# Sensado.net
KiCad netlist of a schematic drawn in Altium Designer
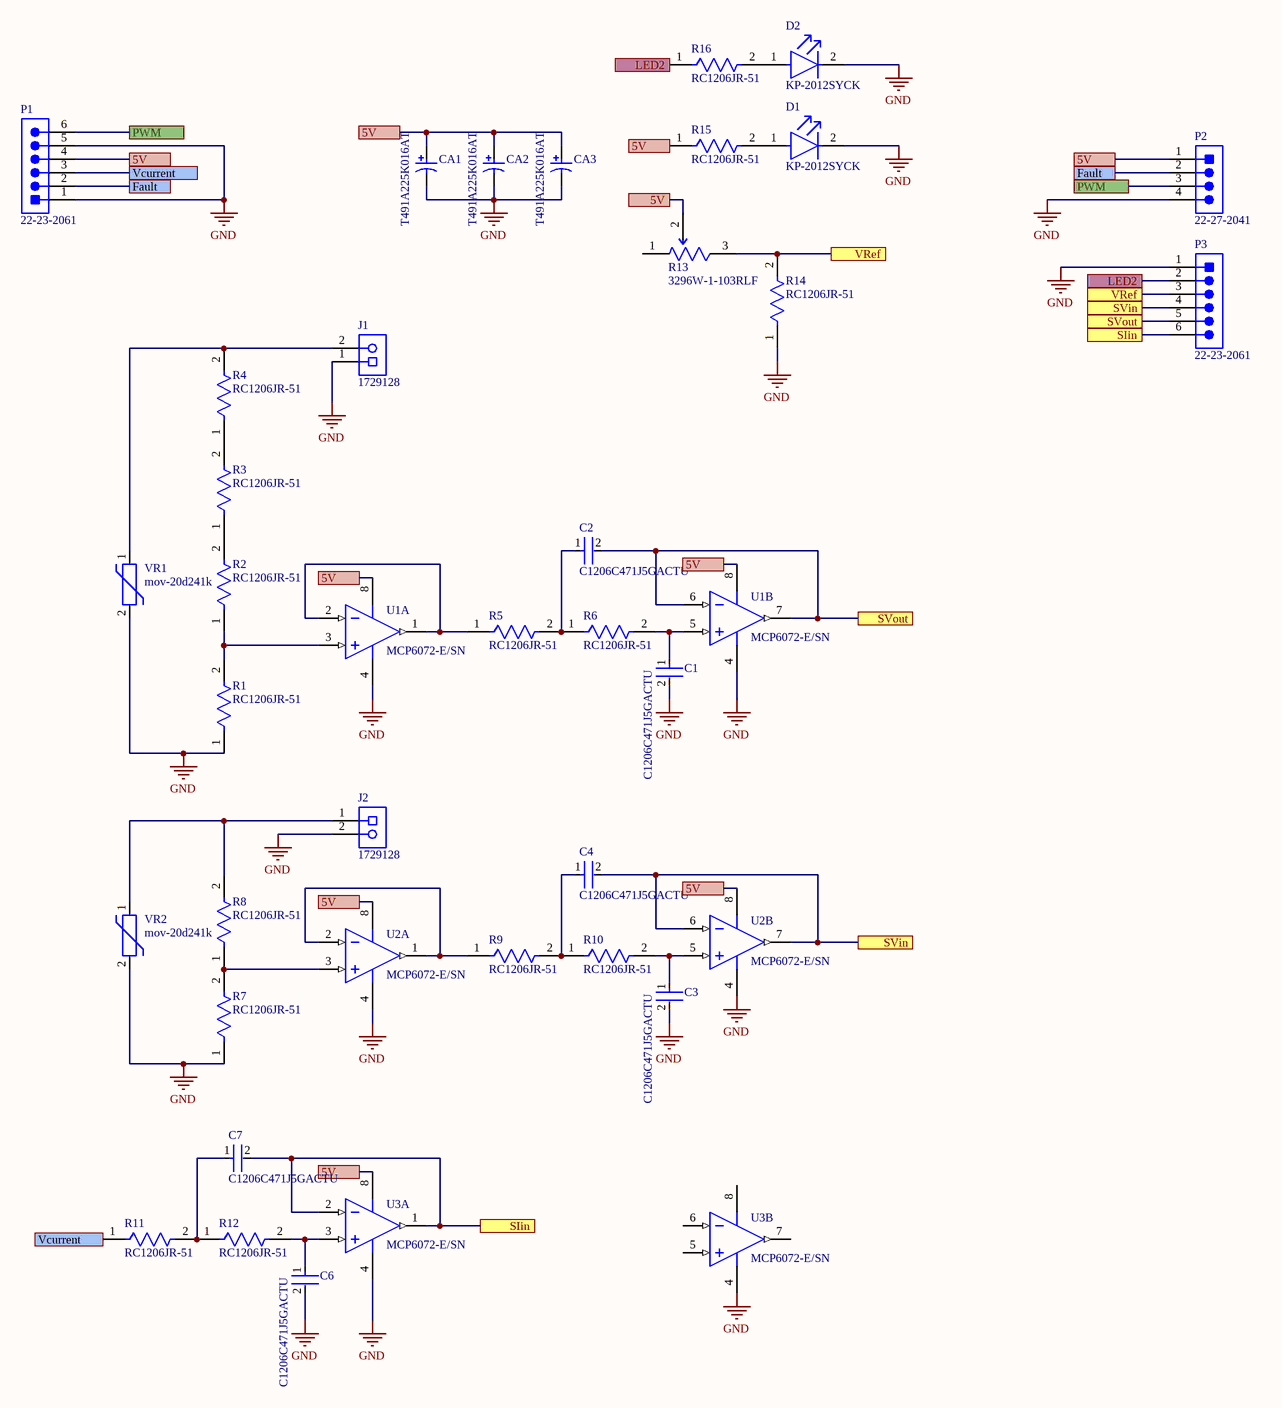
[diagram p0: Sensado.SchDoc]

(export (version "E")
  (design (tool "Eeschema 10.0.6"))
  (components
    (comp (ref "C1")
      (value "C1206C471J5GACTU")
      (footprint "FP-C1206C-EB-IPC_B")
      (description "1206 C 470pF Ceramic Multilayer Capacitor; 50 V; +125degC; C0G Dielectric; +/-5%")
      (fields
        (field (name "TOLERANCE") "0.05")
        (field (name "OCTOPART") "https://octopart.com/c1206c471j5gactu-kemet-123947")
      )
      (libsource (lib "Altium Content Vault") (part "b4654b650e69147ec39a6b967a45e02"))
    )
    (comp (ref "C2")
      (value "C1206C471J5GACTU")
      (footprint "FP-C1206C-EB-IPC_B")
      (description "1206 C 470pF Ceramic Multilayer Capacitor; 50 V; +125degC; C0G Dielectric; +/-5%")
      (fields
        (field (name "TOLERANCE") "0.05")
        (field (name "OCTOPART") "https://octopart.com/c1206c471j5gactu-kemet-123947")
      )
      (libsource (lib "Altium Content Vault") (part "b4654b650e69147ec39a6b967a45e02"))
    )
    (comp (ref "C3")
      (value "C1206C471J5GACTU")
      (footprint "FP-C1206C-EB-IPC_B")
      (description "1206 C 470pF Ceramic Multilayer Capacitor; 50 V; +125degC; C0G Dielectric; +/-5%")
      (fields
        (field (name "TOLERANCE") "0.05")
        (field (name "OCTOPART") "https://octopart.com/c1206c471j5gactu-kemet-123947")
      )
      (libsource (lib "Altium Content Vault") (part "b4654b650e69147ec39a6b967a45e02"))
    )
    (comp (ref "C4")
      (value "C1206C471J5GACTU")
      (footprint "FP-C1206C-EB-IPC_B")
      (description "1206 C 470pF Ceramic Multilayer Capacitor; 50 V; +125degC; C0G Dielectric; +/-5%")
      (fields
        (field (name "TOLERANCE") "0.05")
        (field (name "OCTOPART") "https://octopart.com/c1206c471j5gactu-kemet-123947")
      )
      (libsource (lib "Altium Content Vault") (part "b4654b650e69147ec39a6b967a45e02"))
    )
    (comp (ref "C6")
      (value "C1206C471J5GACTU")
      (footprint "FP-C1206C-EB-IPC_B")
      (description "1206 C 470pF Ceramic Multilayer Capacitor; 50 V; +125degC; C0G Dielectric; +/-5%")
      (fields
        (field (name "TOLERANCE") "0.05")
        (field (name "OCTOPART") "https://octopart.com/c1206c471j5gactu-kemet-123947")
      )
      (libsource (lib "Altium Content Vault") (part "b4654b650e69147ec39a6b967a45e02"))
    )
    (comp (ref "C7")
      (value "C1206C471J5GACTU")
      (footprint "FP-C1206C-EB-IPC_B")
      (description "1206 C 470pF Ceramic Multilayer Capacitor; 50 V; +125degC; C0G Dielectric; +/-5%")
      (fields
        (field (name "TOLERANCE") "0.05")
        (field (name "OCTOPART") "https://octopart.com/c1206c471j5gactu-kemet-123947")
      )
      (libsource (lib "Altium Content Vault") (part "b4654b650e69147ec39a6b967a45e02"))
    )
    (comp (ref "CA1")
      (value "T491A225K016AT")
      (footprint "KEMT-T491-A_N")
      (description "Tantalum Capacitor, 2.2 uF, +/- 10%, 16 V, -55 to 125 degC, 2-Pin SMD, RoHS, Tape and Reel")
      (fields (field (name "VOLTAGE") "16VDC") (field (name "MANUFACTURER") "Kemet"))
      (libsource (lib "Altium Content Vault") (part "CAP-P-2"))
    )
    (comp (ref "CA2")
      (value "T491A225K016AT")
      (footprint "KEMT-T491-A_N")
      (description "Tantalum Capacitor, 2.2 uF, +/- 10%, 16 V, -55 to 125 degC, 2-Pin SMD, RoHS, Tape and Reel")
      (fields (field (name "VOLTAGE") "16VDC") (field (name "MANUFACTURER") "Kemet"))
      (libsource (lib "Altium Content Vault") (part "CAP-P-2"))
    )
    (comp (ref "CA3")
      (value "T491A225K016AT")
      (footprint "KEMT-T491-A_N")
      (description "Tantalum Capacitor, 2.2 uF, +/- 10%, 16 V, -55 to 125 degC, 2-Pin SMD, RoHS, Tape and Reel")
      (fields (field (name "VOLTAGE") "16VDC") (field (name "MANUFACTURER") "Kemet"))
      (libsource (lib "Altium Content Vault") (part "CAP-P-2"))
    )
    (comp (ref "D1")
      (value "KP-2012SYCK")
      (footprint "FP-KP-2012SYCK-MFG")
      (description "2.0x1.25mm SMD CHIP LED LAMP")
      (fields
        (field (name "OCTOPART") "https://octopart.com/kp-2012syck-kingbright-5387420")
        (field (name "MANUFACTURER") "KINGBRIGHT")
      )
      (libsource (lib "Altium Content Vault") (part "ab1c01a81903e929fc6c44469aada92"))
    )
    (comp (ref "D2")
      (value "KP-2012SYCK")
      (footprint "FP-KP-2012SYCK-MFG")
      (description "2.0x1.25mm SMD CHIP LED LAMP")
      (fields
        (field (name "OCTOPART") "https://octopart.com/kp-2012syck-kingbright-5387420")
        (field (name "MANUFACTURER") "KINGBRIGHT")
      )
      (libsource (lib "Altium Content Vault") (part "ab1c01a81903e929fc6c44469aada92"))
    )
    (comp (ref "J1")
      (value "1729128")
      (footprint "PHOE-1729128-2_V")
      (description "PCB Terminal Block, 13.5 A, 400 V, 2-Pin THD, RoHS, Bulk")
      (fields (field (name "MANUFACTURER") "Phoenix Contact"))
      (libsource (lib "Altium Content Vault") (part "CN-2P-F-R2"))
    )
    (comp (ref "J2")
      (value "1729128")
      (footprint "PHOE-1729128-2_V")
      (description "PCB Terminal Block, 13.5 A, 400 V, 2-Pin THD, RoHS, Bulk")
      (fields (field (name "MANUFACTURER") "Phoenix Contact"))
      (libsource (lib "") (part "CN-2P-F-R2_1"))
    )
    (comp (ref "P1")
      (value "22-23-2061")
      (footprint "MOLX-22-23-2061_V")
      (fields (field (name "MANUFACTURER") "Molex"))
      (libsource (lib "") (part "CN-1P-M-R6_1"))
    )
    (comp (ref "P2")
      (value "22-27-2041")
      (footprint "MOLX-22-27-2041_V")
      (description "Male Header, Pitch 2.54 mm, 1 x 4 Position, Height 11.7 mm, Tail Length 3.56 mm, RoHS, Bulk")
      (fields (field (name "MANUFACTURER") "Molex"))
      (libsource (lib "Altium Content Vault") (part "CN-1P-M-R4"))
    )
    (comp (ref "P3")
      (value "22-23-2061")
      (footprint "MOLX-22-23-2061_V")
      (fields (field (name "MANUFACTURER") "Molex"))
      (libsource (lib "Altium Content Vault") (part "CN-1P-M-R6"))
    )
    (comp (ref "R1")
      (value "RC1206JR-51")
      (footprint "FP-RC1206-IPC_B")
      (description "RES SMD 51 OHM  1/4W 1206")
      (fields
        (field (name "MANUFACTURER PART NUMBER") "RC1206JR-070RL")
        (field (name "MANUFACTURER") "YAGEO")
      )
      (libsource (lib "Altium Content Vault") (part "1029c3af85768c4190bb7ad29bc67b5"))
    )
    (comp (ref "R2")
      (value "RC1206JR-51")
      (footprint "FP-RC1206-IPC_B")
      (description "RES SMD 51 OHM  1/4W 1206")
      (fields
        (field (name "MANUFACTURER PART NUMBER") "RC1206JR-070RL")
        (field (name "MANUFACTURER") "YAGEO")
      )
      (libsource (lib "Altium Content Vault") (part "1029c3af85768c4190bb7ad29bc67b5"))
    )
    (comp (ref "R3")
      (value "RC1206JR-51")
      (footprint "FP-RC1206-IPC_B")
      (description "RES SMD 51 OHM  1/4W 1206")
      (fields
        (field (name "MANUFACTURER PART NUMBER") "RC1206JR-070RL")
        (field (name "MANUFACTURER") "YAGEO")
      )
      (libsource (lib "Altium Content Vault") (part "1029c3af85768c4190bb7ad29bc67b5"))
    )
    (comp (ref "R4")
      (value "RC1206JR-51")
      (footprint "FP-RC1206-IPC_B")
      (description "RES SMD 51 OHM  1/4W 1206")
      (fields
        (field (name "MANUFACTURER PART NUMBER") "RC1206JR-070RL")
        (field (name "MANUFACTURER") "YAGEO")
      )
      (libsource (lib "Altium Content Vault") (part "1029c3af85768c4190bb7ad29bc67b5"))
    )
    (comp (ref "R5")
      (value "RC1206JR-51")
      (footprint "FP-RC1206-IPC_B")
      (description "RES SMD 51 OHM  1/4W 1206")
      (fields
        (field (name "MANUFACTURER PART NUMBER") "RC1206JR-070RL")
        (field (name "MANUFACTURER") "YAGEO")
      )
      (libsource (lib "Altium Content Vault") (part "1029c3af85768c4190bb7ad29bc67b5"))
    )
    (comp (ref "R6")
      (value "RC1206JR-51")
      (footprint "FP-RC1206-IPC_B")
      (description "RES SMD 51 OHM  1/4W 1206")
      (fields
        (field (name "MANUFACTURER PART NUMBER") "RC1206JR-070RL")
        (field (name "MANUFACTURER") "YAGEO")
      )
      (libsource (lib "Altium Content Vault") (part "1029c3af85768c4190bb7ad29bc67b5"))
    )
    (comp (ref "R7")
      (value "RC1206JR-51")
      (footprint "FP-RC1206-IPC_B")
      (description "RES SMD 51 OHM  1/4W 1206")
      (fields
        (field (name "MANUFACTURER PART NUMBER") "RC1206JR-070RL")
        (field (name "MANUFACTURER") "YAGEO")
      )
      (libsource (lib "Altium Content Vault") (part "1029c3af85768c4190bb7ad29bc67b5"))
    )
    (comp (ref "R8")
      (value "RC1206JR-51")
      (footprint "FP-RC1206-IPC_B")
      (description "RES SMD 51 OHM  1/4W 1206")
      (fields
        (field (name "MANUFACTURER PART NUMBER") "RC1206JR-070RL")
        (field (name "MANUFACTURER") "YAGEO")
      )
      (libsource (lib "Altium Content Vault") (part "1029c3af85768c4190bb7ad29bc67b5"))
    )
    (comp (ref "R9")
      (value "RC1206JR-51")
      (footprint "FP-RC1206-IPC_B")
      (description "RES SMD 51 OHM  1/4W 1206")
      (fields
        (field (name "MANUFACTURER PART NUMBER") "RC1206JR-070RL")
        (field (name "MANUFACTURER") "YAGEO")
      )
      (libsource (lib "Altium Content Vault") (part "1029c3af85768c4190bb7ad29bc67b5"))
    )
    (comp (ref "R10")
      (value "RC1206JR-51")
      (footprint "FP-RC1206-IPC_B")
      (description "RES SMD 51 OHM  1/4W 1206")
      (fields
        (field (name "MANUFACTURER PART NUMBER") "RC1206JR-070RL")
        (field (name "MANUFACTURER") "YAGEO")
      )
      (libsource (lib "Altium Content Vault") (part "1029c3af85768c4190bb7ad29bc67b5"))
    )
    (comp (ref "R11")
      (value "RC1206JR-51")
      (footprint "FP-RC1206-IPC_B")
      (description "RES SMD 51 OHM  1/4W 1206")
      (fields
        (field (name "MANUFACTURER PART NUMBER") "RC1206JR-070RL")
        (field (name "MANUFACTURER") "YAGEO")
      )
      (libsource (lib "Altium Content Vault") (part "1029c3af85768c4190bb7ad29bc67b5"))
    )
    (comp (ref "R12")
      (value "RC1206JR-51")
      (footprint "FP-RC1206-IPC_B")
      (description "RES SMD 51 OHM  1/4W 1206")
      (fields
        (field (name "MANUFACTURER PART NUMBER") "RC1206JR-070RL")
        (field (name "MANUFACTURER") "YAGEO")
      )
      (libsource (lib "Altium Content Vault") (part "1029c3af85768c4190bb7ad29bc67b5"))
    )
    (comp (ref "R13")
      (value "3296W-1-103RLF")
      (footprint "FP-3296W-MFG")
      (description "TRIMMER 10K OHM 0.5W PC PIN TOP")
      (fields (field (name "TOLERANCE") "10%"))
      (libsource (lib "Altium Content Vault") (part "194907ebf2981c0cdd5d9631a0af656"))
    )
    (comp (ref "R14")
      (value "RC1206JR-51")
      (footprint "FP-RC1206-IPC_B")
      (description "RES SMD 51 OHM  1/4W 1206")
      (fields
        (field (name "MANUFACTURER PART NUMBER") "RC1206JR-070RL")
        (field (name "MANUFACTURER") "YAGEO")
      )
      (libsource (lib "Altium Content Vault") (part "1029c3af85768c4190bb7ad29bc67b5"))
    )
    (comp (ref "R15")
      (value "RC1206JR-51")
      (footprint "FP-RC1206-IPC_B")
      (description "RES SMD 51 OHM  1/4W 1206")
      (fields
        (field (name "MANUFACTURER PART NUMBER") "RC1206JR-070RL")
        (field (name "MANUFACTURER") "YAGEO")
      )
      (libsource (lib "Altium Content Vault") (part "1029c3af85768c4190bb7ad29bc67b5"))
    )
    (comp (ref "R16")
      (value "RC1206JR-51")
      (footprint "FP-RC1206-IPC_B")
      (description "RES SMD 51 OHM  1/4W 1206")
      (fields
        (field (name "MANUFACTURER PART NUMBER") "RC1206JR-070RL")
        (field (name "MANUFACTURER") "YAGEO")
      )
      (libsource (lib "Altium Content Vault") (part "1029c3af85768c4190bb7ad29bc67b5"))
    )
    (comp (ref "U1")
      (value "MCP6072-E/SN")
      (footprint "SOIC-SN8_L")
      (description "110 渭A, High Precision Dual Op Amp, 8-Pin SOIC, Extended Temperature")
      (libsource (lib "Altium Content Vault") (part "AMP-OPA-MCP6042-IL8"))
    )
    (comp (ref "U2")
      (value "MCP6072-E/SN")
      (footprint "SOIC-SN8_L")
      (description "110 渭A, High Precision Dual Op Amp, 8-Pin SOIC, Extended Temperature")
      (libsource (lib "Altium Content Vault") (part "AMP-OPA-MCP6042-IL8"))
    )
    (comp (ref "U3")
      (value "MCP6072-E/SN")
      (footprint "SOIC-SN8_L")
      (description "110 渭A, High Precision Dual Op Amp, 8-Pin SOIC, Extended Temperature")
      (libsource (lib "Altium Content Vault") (part "AMP-OPA-MCP6042-IL8"))
    )
    (comp (ref "VR1")
      (value "mov-20d241k")
      (footprint "Axial 10MM")
      (description "Varistor de oxido de metal.\r\nVoltaje AC (RMS): 150V.\r\nVoltaje DC: 200V.")
      (libsource (lib "20D241K") (part "mov-20d241k"))
    )
    (comp (ref "VR2")
      (value "mov-20d241k")
      (footprint "Axial 10MM")
      (description "Varistor de oxido de metal.\r\nVoltaje AC (RMS): 150V.\r\nVoltaje DC: 200V.")
      (libsource (lib "20D241K") (part "mov-20d241k"))
    )
  )
  (nets
    (net (code "1") (name "/5V") (class "Default")
      (node (ref "CA1") (pin "1") (pinfunction "1_1") (pintype "passive"))
      (node (ref "CA2") (pin "1") (pinfunction "1_1") (pintype "passive"))
      (node (ref "CA3") (pin "1") (pinfunction "1_1") (pintype "passive"))
      (node (ref "P1") (pin "4") (pinfunction "4_4") (pintype "passive"))
      (node (ref "P2") (pin "1") (pinfunction "1_1") (pintype "passive"))
      (node (ref "R13") (pin "2") (pinfunction "WIPER_2") (pintype "passive"))
      (node (ref "R15") (pin "1") (pinfunction "1_1") (pintype "passive"))
      (node (ref "U1") (pin "8") (pinfunction "VDD_8") (pintype "power_in"))
      (node (ref "U2") (pin "8") (pinfunction "VDD_8") (pintype "power_in"))
      (node (ref "U3") (pin "8") (pinfunction "VDD_8") (pintype "power_in"))
    )
    (net (code "2") (name "/Fault") (class "Default")
      (node (ref "P1") (pin "2") (pinfunction "2_2") (pintype "passive"))
      (node (ref "P2") (pin "2") (pinfunction "2_2") (pintype "passive"))
    )
    (net (code "3") (name "/LED2") (class "Default")
      (node (ref "P3") (pin "2") (pinfunction "2_2") (pintype "passive"))
      (node (ref "R16") (pin "1") (pinfunction "1_1") (pintype "passive"))
    )
    (net (code "4") (name "/PWM") (class "Default")
      (node (ref "P1") (pin "6") (pinfunction "6_6") (pintype "passive"))
      (node (ref "P2") (pin "3") (pinfunction "3_3") (pintype "passive"))
    )
    (net (code "5") (name "/SIin") (class "Default")
      (node (ref "C7") (pin "2") (pinfunction "2_2") (pintype "passive"))
      (node (ref "P3") (pin "6") (pinfunction "6_6") (pintype "passive"))
      (node (ref "U3") (pin "1") (pinfunction "VOUTA_1") (pintype "output"))
      (node (ref "U3") (pin "2") (pinfunction "VINA-_2") (pintype "input"))
    )
    (net (code "6") (name "/SVin") (class "Default")
      (node (ref "C4") (pin "2") (pinfunction "2_2") (pintype "passive"))
      (node (ref "P3") (pin "4") (pinfunction "4_4") (pintype "passive"))
      (node (ref "U2") (pin "6") (pinfunction "VINB-_6") (pintype "input"))
      (node (ref "U2") (pin "7") (pinfunction "VOUTB_7") (pintype "output"))
    )
    (net (code "7") (name "/SVout") (class "Default")
      (node (ref "C2") (pin "2") (pinfunction "2_2") (pintype "passive"))
      (node (ref "P3") (pin "5") (pinfunction "5_5") (pintype "passive"))
      (node (ref "U1") (pin "6") (pinfunction "VINB-_6") (pintype "input"))
      (node (ref "U1") (pin "7") (pinfunction "VOUTB_7") (pintype "output"))
    )
    (net (code "8") (name "/VRef") (class "Default")
      (node (ref "P3") (pin "3") (pinfunction "3_3") (pintype "passive"))
      (node (ref "R13") (pin "3") (pinfunction "CW_3") (pintype "passive"))
      (node (ref "R14") (pin "2") (pinfunction "2_2") (pintype "passive"))
    )
    (net (code "9") (name "/Vcurrent") (class "Default")
      (node (ref "P1") (pin "3") (pinfunction "3_3") (pintype "passive"))
      (node (ref "R11") (pin "1") (pinfunction "1_1") (pintype "passive"))
    )
    (net (code "10") (name "GND") (class "Default")
      (node (ref "C1") (pin "2") (pinfunction "2_2") (pintype "passive"))
      (node (ref "C3") (pin "2") (pinfunction "2_2") (pintype "passive"))
      (node (ref "C6") (pin "2") (pinfunction "2_2") (pintype "passive"))
      (node (ref "CA1") (pin "2") (pinfunction "2_2") (pintype "passive"))
      (node (ref "CA2") (pin "2") (pinfunction "2_2") (pintype "passive"))
      (node (ref "CA3") (pin "2") (pinfunction "2_2") (pintype "passive"))
      (node (ref "D1") (pin "2") (pinfunction "C_2") (pintype "passive"))
      (node (ref "D2") (pin "2") (pinfunction "C_2") (pintype "passive"))
      (node (ref "J1") (pin "1") (pinfunction "1_1") (pintype "passive"))
      (node (ref "J2") (pin "2") (pinfunction "2_2") (pintype "passive"))
      (node (ref "P1") (pin "1") (pinfunction "1_1") (pintype "passive"))
      (node (ref "P1") (pin "5") (pinfunction "5_5") (pintype "passive"))
      (node (ref "P2") (pin "4") (pinfunction "4_4") (pintype "passive"))
      (node (ref "P3") (pin "1") (pinfunction "1_1") (pintype "passive"))
      (node (ref "R1") (pin "1") (pinfunction "1_1") (pintype "passive"))
      (node (ref "R14") (pin "1") (pinfunction "1_1") (pintype "passive"))
      (node (ref "R7") (pin "1") (pinfunction "1_1") (pintype "passive"))
      (node (ref "U1") (pin "4") (pinfunction "VSS_4") (pintype "power_in"))
      (node (ref "U2") (pin "4") (pinfunction "VSS_4") (pintype "power_in"))
      (node (ref "U3") (pin "4") (pinfunction "VSS_4") (pintype "power_in"))
      (node (ref "VR1") (pin "2") (pintype "passive"))
      (node (ref "VR2") (pin "2") (pintype "passive"))
    )
    (net (code "11") (name "Net-(C2-Pad1)") (class "Default")
      (node (ref "C2") (pin "1") (pinfunction "1_1") (pintype "passive"))
      (node (ref "R5") (pin "2") (pinfunction "2_2") (pintype "passive"))
      (node (ref "R6") (pin "1") (pinfunction "1_1") (pintype "passive"))
    )
    (net (code "12") (name "Net-(C4-Pad1)") (class "Default")
      (node (ref "C4") (pin "1") (pinfunction "1_1") (pintype "passive"))
      (node (ref "R10") (pin "1") (pinfunction "1_1") (pintype "passive"))
      (node (ref "R9") (pin "2") (pinfunction "2_2") (pintype "passive"))
    )
    (net (code "13") (name "Net-(C7-Pad1)") (class "Default")
      (node (ref "C7") (pin "1") (pinfunction "1_1") (pintype "passive"))
      (node (ref "R11") (pin "2") (pinfunction "2_2") (pintype "passive"))
      (node (ref "R12") (pin "1") (pinfunction "1_1") (pintype "passive"))
    )
    (net (code "14") (name "Net-(D1-A)") (class "Default")
      (node (ref "D1") (pin "1") (pinfunction "A_1") (pintype "passive"))
      (node (ref "R15") (pin "2") (pinfunction "2_2") (pintype "passive"))
    )
    (net (code "15") (name "Net-(D2-A)") (class "Default")
      (node (ref "D2") (pin "1") (pinfunction "A_1") (pintype "passive"))
      (node (ref "R16") (pin "2") (pinfunction "2_2") (pintype "passive"))
    )
    (net (code "16") (name "Net-(J1-Pad2)") (class "Default")
      (node (ref "J1") (pin "2") (pinfunction "2_2") (pintype "passive"))
      (node (ref "R4") (pin "2") (pinfunction "2_2") (pintype "passive"))
      (node (ref "VR1") (pin "1") (pintype "passive"))
    )
    (net (code "17") (name "Net-(J2-Pad1)") (class "Default")
      (node (ref "J2") (pin "1") (pinfunction "1_1") (pintype "passive"))
      (node (ref "R8") (pin "2") (pinfunction "2_2") (pintype "passive"))
      (node (ref "VR2") (pin "1") (pintype "passive"))
    )
    (net (code "18") (name "Net-(R2-Pad2)") (class "Default")
      (node (ref "R2") (pin "2") (pinfunction "2_2") (pintype "passive"))
      (node (ref "R3") (pin "1") (pinfunction "1_1") (pintype "passive"))
    )
    (net (code "19") (name "Net-(R3-Pad2)") (class "Default")
      (node (ref "R3") (pin "2") (pinfunction "2_2") (pintype "passive"))
      (node (ref "R4") (pin "1") (pinfunction "1_1") (pintype "passive"))
    )
    (net (code "20") (name "Net-(U1A-VINA+)") (class "Default")
      (node (ref "R1") (pin "2") (pinfunction "2_2") (pintype "passive"))
      (node (ref "R2") (pin "1") (pinfunction "1_1") (pintype "passive"))
      (node (ref "U1") (pin "3") (pinfunction "VINA+_3") (pintype "input"))
    )
    (net (code "21") (name "Net-(U1A-VINA-)") (class "Default")
      (node (ref "R5") (pin "1") (pinfunction "1_1") (pintype "passive"))
      (node (ref "U1") (pin "1") (pinfunction "VOUTA_1") (pintype "output"))
      (node (ref "U1") (pin "2") (pinfunction "VINA-_2") (pintype "input"))
    )
    (net (code "22") (name "Net-(U1B-VINB+)") (class "Default")
      (node (ref "C1") (pin "1") (pinfunction "1_1") (pintype "passive"))
      (node (ref "R6") (pin "2") (pinfunction "2_2") (pintype "passive"))
      (node (ref "U1") (pin "5") (pinfunction "VINB+_5") (pintype "input"))
    )
    (net (code "23") (name "Net-(U2A-VINA+)") (class "Default")
      (node (ref "R7") (pin "2") (pinfunction "2_2") (pintype "passive"))
      (node (ref "R8") (pin "1") (pinfunction "1_1") (pintype "passive"))
      (node (ref "U2") (pin "3") (pinfunction "VINA+_3") (pintype "input"))
    )
    (net (code "24") (name "Net-(U2A-VINA-)") (class "Default")
      (node (ref "R9") (pin "1") (pinfunction "1_1") (pintype "passive"))
      (node (ref "U2") (pin "1") (pinfunction "VOUTA_1") (pintype "output"))
      (node (ref "U2") (pin "2") (pinfunction "VINA-_2") (pintype "input"))
    )
    (net (code "25") (name "Net-(U2B-VINB+)") (class "Default")
      (node (ref "C3") (pin "1") (pinfunction "1_1") (pintype "passive"))
      (node (ref "R10") (pin "2") (pinfunction "2_2") (pintype "passive"))
      (node (ref "U2") (pin "5") (pinfunction "VINB+_5") (pintype "input"))
    )
    (net (code "26") (name "Net-(U3A-VINA+)") (class "Default")
      (node (ref "C6") (pin "1") (pinfunction "1_1") (pintype "passive"))
      (node (ref "R12") (pin "2") (pinfunction "2_2") (pintype "passive"))
      (node (ref "U3") (pin "3") (pinfunction "VINA+_3") (pintype "input"))
    )
    (net (code "27") (name "unconnected-(R13-CCW-Pad1)") (class "Default")
      (node (ref "R13") (pin "1") (pinfunction "CCW_1") (pintype "passive"))
    )
    (net (code "28") (name "unconnected-(U3B-VDD-Pad8)") (class "Default")
      (node (ref "U3") (pin "8") (pinfunction "VDD_8") (pintype "power_in"))
    )
    (net (code "29") (name "unconnected-(U3B-VINB+-Pad5)") (class "Default")
      (node (ref "U3") (pin "5") (pinfunction "VINB+_5") (pintype "input"))
    )
    (net (code "30") (name "unconnected-(U3B-VINB--Pad6)") (class "Default")
      (node (ref "U3") (pin "6") (pinfunction "VINB-_6") (pintype "input"))
    )
    (net (code "31") (name "unconnected-(U3B-VOUTB-Pad7)") (class "Default")
      (node (ref "U3") (pin "7") (pinfunction "VOUTB_7") (pintype "output"))
    )
  )
)
